# DSP_Board_Headers.net
KiCad netlist of a schematic drawn in Altium Designer
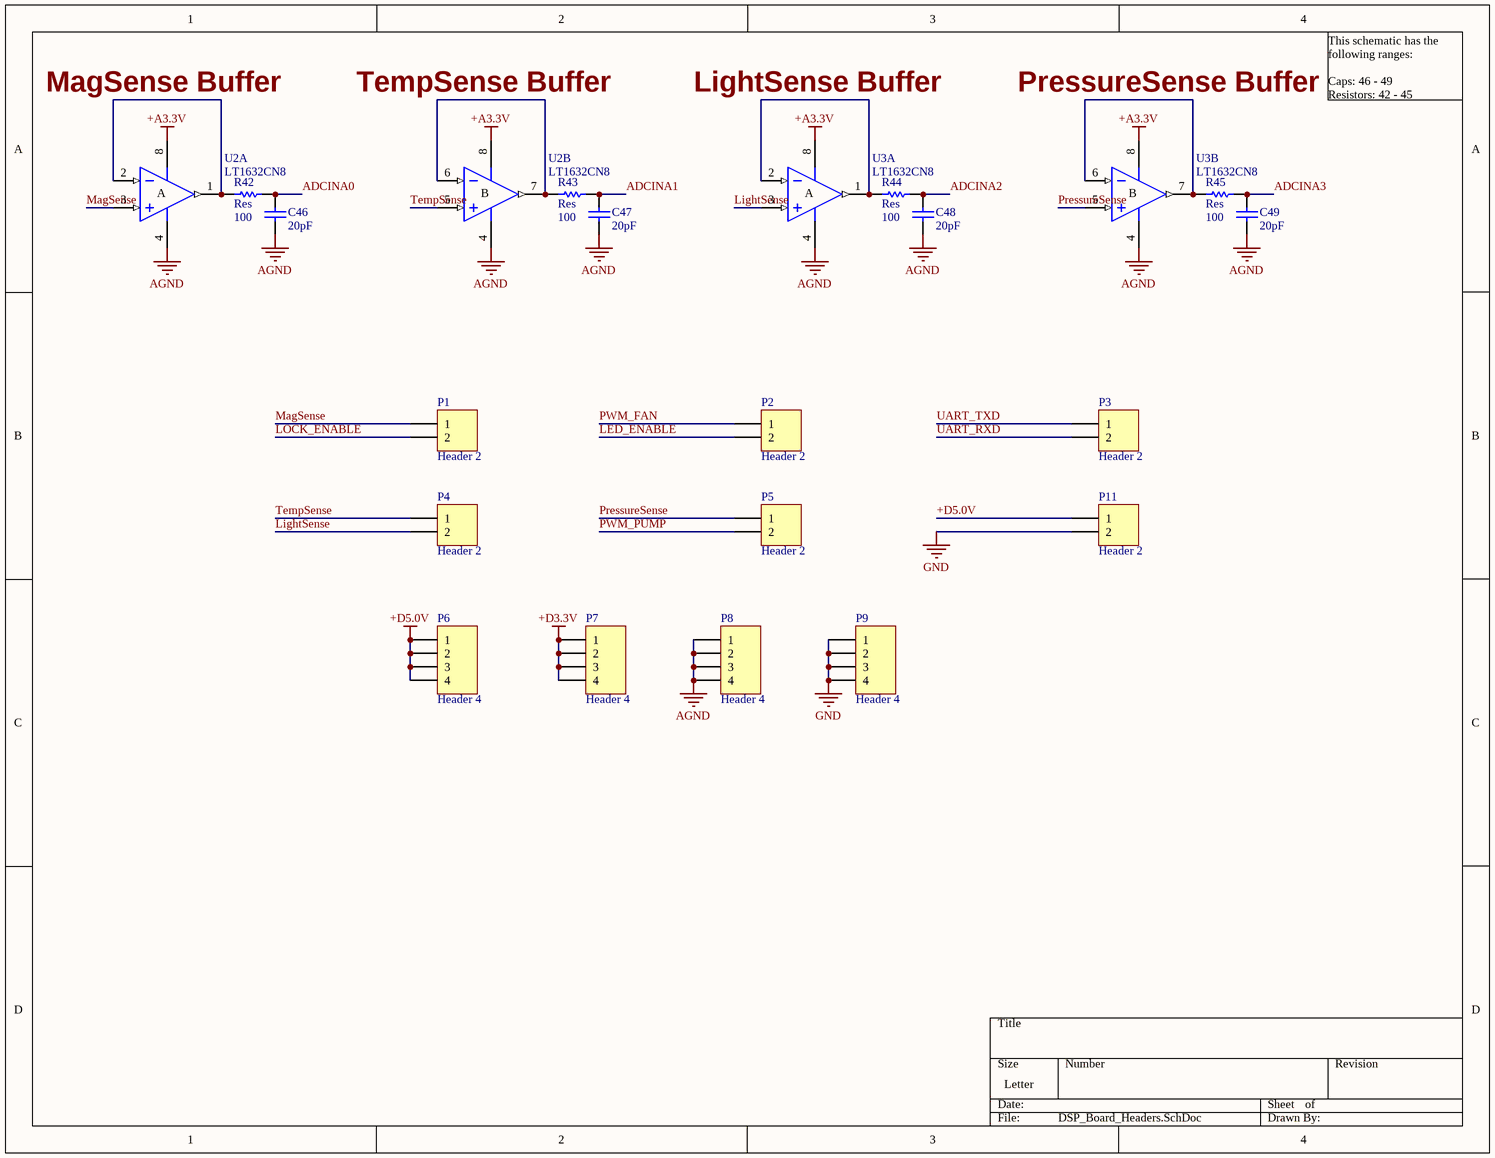
[diagram p0: DSP_Board_Headers.SchDoc]

(export (version "E")
  (design (tool "Eeschema 10.0.6"))
  (components
    (comp (ref "C46")
      (value "20pF")
      (footprint "0805")
      (description "Capacitor (Semiconductor SIM Model)")
      (fields (field (name "Comment") "Cap Semi") (field (name "PUBLISHER") "Altium Limited"))
      (libsource (lib "TMS320F28335GF") (part "Cap Semi"))
    )
    (comp (ref "C47")
      (value "20pF")
      (footprint "0805")
      (description "Capacitor (Semiconductor SIM Model)")
      (fields (field (name "Comment") "Cap Semi") (field (name "PUBLISHER") "Altium Limited"))
      (libsource (lib "TMS320F28335GF") (part "Cap Semi"))
    )
    (comp (ref "C48")
      (value "20pF")
      (footprint "0805")
      (description "Capacitor (Semiconductor SIM Model)")
      (fields (field (name "Comment") "Cap Semi") (field (name "PUBLISHER") "Altium Limited"))
      (libsource (lib "TMS320F28335GF") (part "Cap Semi"))
    )
    (comp (ref "C49")
      (value "20pF")
      (footprint "0805")
      (description "Capacitor (Semiconductor SIM Model)")
      (fields (field (name "Comment") "Cap Semi") (field (name "PUBLISHER") "Altium Limited"))
      (libsource (lib "TMS320F28335GF") (part "Cap Semi"))
    )
    (comp (ref "P1")
      (value "Header 2")
      (footprint "HDR1X2")
      (description "Header, 2-Pin")
      (fields (field (name "PUBLISHER") "Altium Limited"))
      (libsource (lib "Miscellaneous Connectors") (part "Header 2"))
    )
    (comp (ref "P2")
      (value "Header 2")
      (footprint "HDR1X2")
      (description "Header, 2-Pin")
      (fields (field (name "PUBLISHER") "Altium Limited"))
      (libsource (lib "Miscellaneous Connectors") (part "Header 2"))
    )
    (comp (ref "P3")
      (value "Header 2")
      (footprint "HDR1X2")
      (description "Header, 2-Pin")
      (fields (field (name "PUBLISHER") "Altium Limited"))
      (libsource (lib "Miscellaneous Connectors") (part "Header 2"))
    )
    (comp (ref "P4")
      (value "Header 2")
      (footprint "HDR1X2")
      (description "Header, 2-Pin")
      (fields (field (name "PUBLISHER") "Altium Limited"))
      (libsource (lib "Miscellaneous Connectors") (part "Header 2"))
    )
    (comp (ref "P5")
      (value "Header 2")
      (footprint "HDR1X2")
      (description "Header, 2-Pin")
      (fields (field (name "PUBLISHER") "Altium Limited"))
      (libsource (lib "Miscellaneous Connectors") (part "Header 2"))
    )
    (comp (ref "P6")
      (value "Header 4")
      (footprint "HDR1X4")
      (description "Header, 4-Pin")
      (fields (field (name "PUBLISHER") "Altium Limited"))
      (libsource (lib "Miscellaneous Connectors") (part "Header 4"))
    )
    (comp (ref "P7")
      (value "Header 4")
      (footprint "HDR1X4")
      (description "Header, 4-Pin")
      (fields (field (name "PUBLISHER") "Altium Limited"))
      (libsource (lib "Miscellaneous Connectors") (part "Header 4"))
    )
    (comp (ref "P8")
      (value "Header 4")
      (footprint "HDR1X4")
      (description "Header, 4-Pin")
      (fields (field (name "PUBLISHER") "Altium Limited"))
      (libsource (lib "Miscellaneous Connectors") (part "Header 4"))
    )
    (comp (ref "P9")
      (value "Header 4")
      (footprint "HDR1X4")
      (description "Header, 4-Pin")
      (fields (field (name "PUBLISHER") "Altium Limited"))
      (libsource (lib "Miscellaneous Connectors") (part "Header 4"))
    )
    (comp (ref "P11")
      (value "Header 2")
      (footprint "HDR1X2")
      (description "Header, 2-Pin")
      (fields (field (name "PUBLISHER") "Altium Limited"))
      (libsource (lib "Miscellaneous Connectors") (part "Header 2"))
    )
    (comp (ref "R42")
      (value "Res")
      (footprint "0805")
      (description "Semiconductor Resistor")
      (fields (field (name "ALTIUM_VALUE") "100") (field (name "PUBLISHER") "Altium Limited"))
      (libsource (lib "TMS320F28335GF") (part "Res Semi"))
    )
    (comp (ref "R43")
      (value "Res")
      (footprint "0805")
      (description "Semiconductor Resistor")
      (fields (field (name "ALTIUM_VALUE") "100") (field (name "PUBLISHER") "Altium Limited"))
      (libsource (lib "TMS320F28335GF") (part "Res Semi"))
    )
    (comp (ref "R44")
      (value "Res")
      (footprint "0805")
      (description "Semiconductor Resistor")
      (fields (field (name "ALTIUM_VALUE") "100") (field (name "PUBLISHER") "Altium Limited"))
      (libsource (lib "TMS320F28335GF") (part "Res Semi"))
    )
    (comp (ref "R45")
      (value "Res")
      (footprint "0805")
      (description "Semiconductor Resistor")
      (fields (field (name "ALTIUM_VALUE") "100") (field (name "PUBLISHER") "Altium Limited"))
      (libsource (lib "TMS320F28335GF") (part "Res Semi"))
    )
    (comp (ref "U2")
      (value "LT1632CN8")
      (footprint "DIP-8")
      (description "45MHz, 45V/µs, Dual Rail-to-Rail Input and Output Precision Operational Amplifier")
      (fields (field (name "PUBLISHER") "Altium Limited"))
      (libsource (lib "ECE LIB new") (part "LT1632CN8"))
    )
    (comp (ref "U3")
      (value "LT1632CN8")
      (footprint "DIP-8")
      (description "45MHz, 45V/µs, Dual Rail-to-Rail Input and Output Precision Operational Amplifier")
      (fields (field (name "PUBLISHER") "Altium Limited"))
      (libsource (lib "ECE LIB new") (part "LT1632CN8"))
    )
  )
  (nets
    (net (code "1") (name "+A3.3V") (class "Default")
      (node (ref "U2") (pin "8") (pinfunction "V+_8") (pintype "power_in"))
      (node (ref "U3") (pin "8") (pinfunction "V+_8") (pintype "power_in"))
    )
    (net (code "2") (name "+D3.3V") (class "Default")
      (node (ref "P7") (pin "1") (pinfunction "1_1") (pintype "passive"))
      (node (ref "P7") (pin "2") (pinfunction "2_2") (pintype "passive"))
      (node (ref "P7") (pin "3") (pinfunction "3_3") (pintype "passive"))
      (node (ref "P7") (pin "4") (pinfunction "4_4") (pintype "passive"))
    )
    (net (code "3") (name "+D5.0V") (class "Default")
      (node (ref "P11") (pin "1") (pinfunction "1_1") (pintype "passive"))
      (node (ref "P6") (pin "1") (pinfunction "1_1") (pintype "passive"))
      (node (ref "P6") (pin "2") (pinfunction "2_2") (pintype "passive"))
      (node (ref "P6") (pin "3") (pinfunction "3_3") (pintype "passive"))
      (node (ref "P6") (pin "4") (pinfunction "4_4") (pintype "passive"))
    )
    (net (code "4") (name "/ADCINA0") (class "Default")
      (node (ref "C46") (pin "2") (pinfunction "2_2") (pintype "passive"))
      (node (ref "R42") (pin "2") (pinfunction "2_2") (pintype "passive"))
    )
    (net (code "5") (name "/ADCINA1") (class "Default")
      (node (ref "C47") (pin "2") (pinfunction "2_2") (pintype "passive"))
      (node (ref "R43") (pin "2") (pinfunction "2_2") (pintype "passive"))
    )
    (net (code "6") (name "/ADCINA2") (class "Default")
      (node (ref "C48") (pin "2") (pinfunction "2_2") (pintype "passive"))
      (node (ref "R44") (pin "2") (pinfunction "2_2") (pintype "passive"))
    )
    (net (code "7") (name "/ADCINA3") (class "Default")
      (node (ref "C49") (pin "2") (pinfunction "2_2") (pintype "passive"))
      (node (ref "R45") (pin "2") (pinfunction "2_2") (pintype "passive"))
    )
    (net (code "8") (name "/LED_ENABLE") (class "Default")
      (node (ref "P2") (pin "2") (pinfunction "2_2") (pintype "passive"))
    )
    (net (code "9") (name "/LOCK_ENABLE") (class "Default")
      (node (ref "P1") (pin "2") (pinfunction "2_2") (pintype "passive"))
    )
    (net (code "10") (name "/LightSense") (class "Default")
      (node (ref "P4") (pin "2") (pinfunction "2_2") (pintype "passive"))
      (node (ref "U3") (pin "3") (pinfunction "IN+_3") (pintype "input"))
    )
    (net (code "11") (name "/MagSense") (class "Default")
      (node (ref "P1") (pin "1") (pinfunction "1_1") (pintype "passive"))
      (node (ref "U2") (pin "3") (pinfunction "IN+_3") (pintype "input"))
    )
    (net (code "12") (name "/PWM_FAN") (class "Default")
      (node (ref "P2") (pin "1") (pinfunction "1_1") (pintype "passive"))
    )
    (net (code "13") (name "/PWM_PUMP") (class "Default")
      (node (ref "P5") (pin "2") (pinfunction "2_2") (pintype "passive"))
    )
    (net (code "14") (name "/PressureSense") (class "Default")
      (node (ref "P5") (pin "1") (pinfunction "1_1") (pintype "passive"))
      (node (ref "U3") (pin "5") (pinfunction "IN+_5") (pintype "input"))
    )
    (net (code "15") (name "/TempSense") (class "Default")
      (node (ref "P4") (pin "1") (pinfunction "1_1") (pintype "passive"))
      (node (ref "U2") (pin "5") (pinfunction "IN+_5") (pintype "input"))
    )
    (net (code "16") (name "/UART_RXD") (class "Default")
      (node (ref "P3") (pin "2") (pinfunction "2_2") (pintype "passive"))
    )
    (net (code "17") (name "/UART_TXD") (class "Default")
      (node (ref "P3") (pin "1") (pinfunction "1_1") (pintype "passive"))
    )
    (net (code "18") (name "AGND") (class "Default")
      (node (ref "C46") (pin "1") (pinfunction "1_1") (pintype "passive"))
      (node (ref "C47") (pin "1") (pinfunction "1_1") (pintype "passive"))
      (node (ref "C48") (pin "1") (pinfunction "1_1") (pintype "passive"))
      (node (ref "C49") (pin "1") (pinfunction "1_1") (pintype "passive"))
      (node (ref "P8") (pin "1") (pinfunction "1_1") (pintype "passive"))
      (node (ref "P8") (pin "2") (pinfunction "2_2") (pintype "passive"))
      (node (ref "P8") (pin "3") (pinfunction "3_3") (pintype "passive"))
      (node (ref "P8") (pin "4") (pinfunction "4_4") (pintype "passive"))
      (node (ref "U2") (pin "4") (pinfunction "V-_4") (pintype "power_in"))
      (node (ref "U3") (pin "4") (pinfunction "V-_4") (pintype "power_in"))
    )
    (net (code "19") (name "GND") (class "Default")
      (node (ref "P11") (pin "2") (pinfunction "2_2") (pintype "passive"))
      (node (ref "P9") (pin "1") (pinfunction "1_1") (pintype "passive"))
      (node (ref "P9") (pin "2") (pinfunction "2_2") (pintype "passive"))
      (node (ref "P9") (pin "3") (pinfunction "3_3") (pintype "passive"))
      (node (ref "P9") (pin "4") (pinfunction "4_4") (pintype "passive"))
    )
    (net (code "20") (name "Net-(U2A-IN-)") (class "Default")
      (node (ref "R42") (pin "1") (pinfunction "1_1") (pintype "passive"))
      (node (ref "U2") (pin "1") (pinfunction "OUT_1") (pintype "output"))
      (node (ref "U2") (pin "2") (pinfunction "IN-_2") (pintype "input"))
    )
    (net (code "21") (name "Net-(U2B-IN-)") (class "Default")
      (node (ref "R43") (pin "1") (pinfunction "1_1") (pintype "passive"))
      (node (ref "U2") (pin "6") (pinfunction "IN-_6") (pintype "input"))
      (node (ref "U2") (pin "7") (pinfunction "OUT_7") (pintype "output"))
    )
    (net (code "22") (name "Net-(U3A-IN-)") (class "Default")
      (node (ref "R44") (pin "1") (pinfunction "1_1") (pintype "passive"))
      (node (ref "U3") (pin "1") (pinfunction "OUT_1") (pintype "output"))
      (node (ref "U3") (pin "2") (pinfunction "IN-_2") (pintype "input"))
    )
    (net (code "23") (name "Net-(U3B-IN-)") (class "Default")
      (node (ref "R45") (pin "1") (pinfunction "1_1") (pintype "passive"))
      (node (ref "U3") (pin "6") (pinfunction "IN-_6") (pintype "input"))
      (node (ref "U3") (pin "7") (pinfunction "OUT_7") (pintype "output"))
    )
  )
)
